# 4022_counter.net
KiCad netlist of a schematic drawn in EAGLE
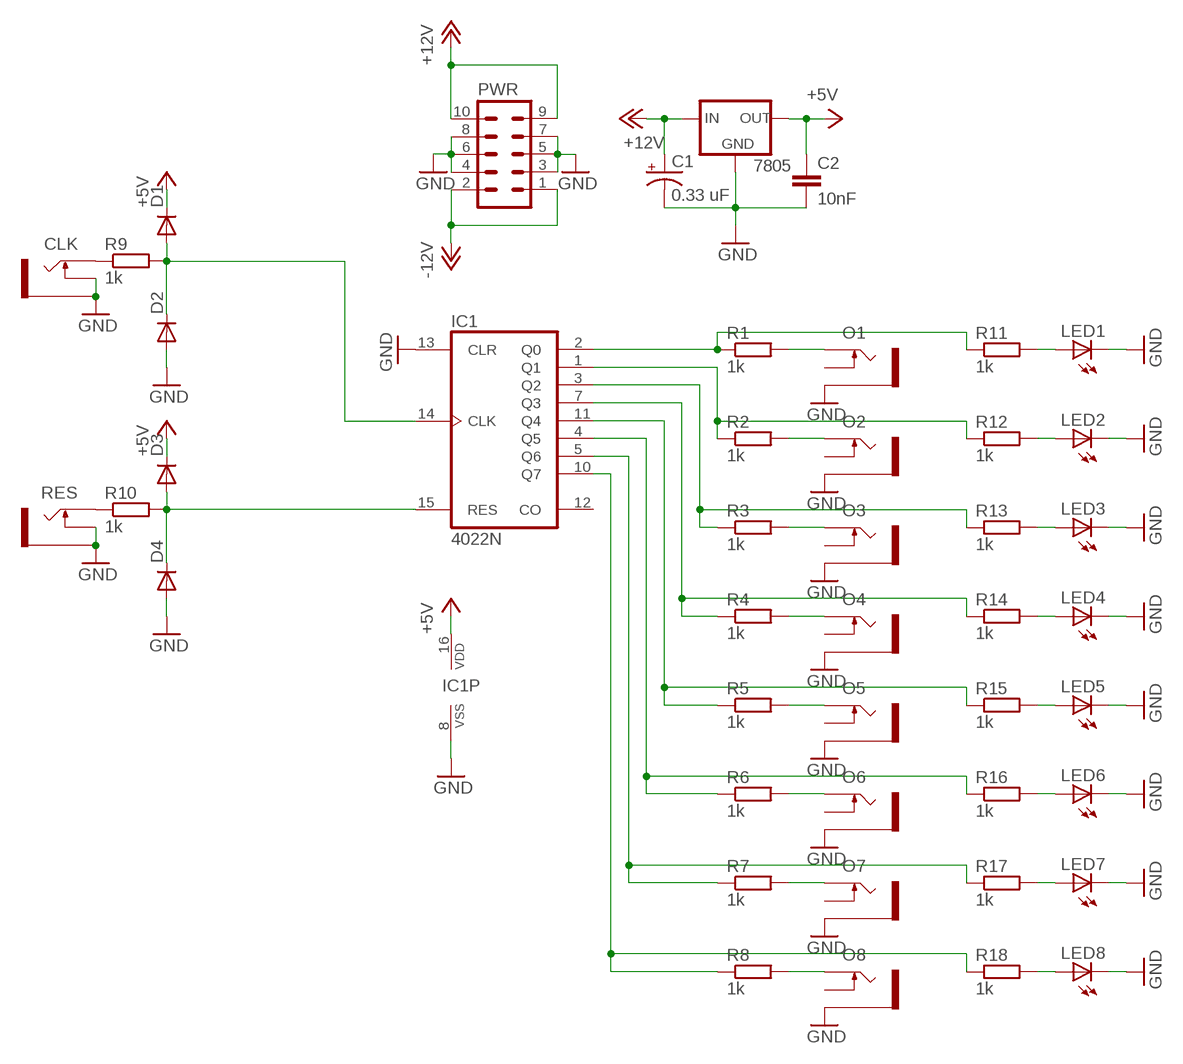
[diagram p0: schematic, sheet 1]

(export (version "E")
  (design (tool "Eeschema 10.0.6"))
  (components
    (comp (ref "7805")
      (value "78XXS")
      (footprint "eagle-import:78XXS")
      (libsource (lib "eagle-import") (part "78XXS"))
    )
    (comp (ref "C1")
      (value "0.33 uF")
      (footprint "eagle-import:E2,5-7")
      (libsource (lib "eagle-import") (part "CPOL-USE2.5-7"))
    )
    (comp (ref "C2")
      (value "10nF")
      (footprint "eagle-import:CAP-PTH-10MM")
      (libsource (lib "eagle-import") (part "10NF-PTH-10MM-10000V-1-%"))
    )
    (comp (ref "CLK")
      (value "THONKICONNNEW")
      (footprint "eagle-import:WQP-PJ301M-12_JACK")
      (libsource (lib "eagle-import") (part "THONKICONNNEW"))
    )
    (comp (ref "D1")
      (value "SMALL_DIODEDO35-7")
      (footprint "eagle-import:DO35-7")
      (libsource (lib "eagle-import") (part "SMALL_DIODEDO35-7"))
    )
    (comp (ref "D2")
      (value "SMALL_DIODEDO35-7")
      (footprint "eagle-import:DO35-7")
      (libsource (lib "eagle-import") (part "SMALL_DIODEDO35-7"))
    )
    (comp (ref "D3")
      (value "SMALL_DIODEDO35-7")
      (footprint "eagle-import:DO35-7")
      (libsource (lib "eagle-import") (part "SMALL_DIODEDO35-7"))
    )
    (comp (ref "D4")
      (value "SMALL_DIODEDO35-7")
      (footprint "eagle-import:DO35-7")
      (libsource (lib "eagle-import") (part "SMALL_DIODEDO35-7"))
    )
    (comp (ref "IC1")
      (value "4022N")
      (footprint "eagle-import:DIL16")
      (libsource (lib "eagle-import") (part "4022N"))
    )
    (comp (ref "LED1")
      (value "LED3MM")
      (footprint "eagle-import:LED3MM")
      (libsource (lib "eagle-import") (part "LED3MM"))
    )
    (comp (ref "LED2")
      (value "LED3MM")
      (footprint "eagle-import:LED3MM")
      (libsource (lib "eagle-import") (part "LED3MM"))
    )
    (comp (ref "LED3")
      (value "LED3MM")
      (footprint "eagle-import:LED3MM")
      (libsource (lib "eagle-import") (part "LED3MM"))
    )
    (comp (ref "LED4")
      (value "LED3MM")
      (footprint "eagle-import:LED3MM")
      (libsource (lib "eagle-import") (part "LED3MM"))
    )
    (comp (ref "LED5")
      (value "LED3MM")
      (footprint "eagle-import:LED3MM")
      (libsource (lib "eagle-import") (part "LED3MM"))
    )
    (comp (ref "LED6")
      (value "LED3MM")
      (footprint "eagle-import:LED3MM")
      (libsource (lib "eagle-import") (part "LED3MM"))
    )
    (comp (ref "LED7")
      (value "LED3MM")
      (footprint "eagle-import:LED3MM")
      (libsource (lib "eagle-import") (part "LED3MM"))
    )
    (comp (ref "LED8")
      (value "LED3MM")
      (footprint "eagle-import:LED3MM")
      (libsource (lib "eagle-import") (part "LED3MM"))
    )
    (comp (ref "O1")
      (value "THONKICONNNEW")
      (footprint "eagle-import:WQP-PJ301M-12_JACK")
      (libsource (lib "eagle-import") (part "THONKICONNNEW"))
    )
    (comp (ref "O2")
      (value "THONKICONNNEW")
      (footprint "eagle-import:WQP-PJ301M-12_JACK")
      (libsource (lib "eagle-import") (part "THONKICONNNEW"))
    )
    (comp (ref "O3")
      (value "THONKICONNNEW")
      (footprint "eagle-import:WQP-PJ301M-12_JACK")
      (libsource (lib "eagle-import") (part "THONKICONNNEW"))
    )
    (comp (ref "O4")
      (value "THONKICONNNEW")
      (footprint "eagle-import:WQP-PJ301M-12_JACK")
      (libsource (lib "eagle-import") (part "THONKICONNNEW"))
    )
    (comp (ref "O5")
      (value "THONKICONNNEW")
      (footprint "eagle-import:WQP-PJ301M-12_JACK")
      (libsource (lib "eagle-import") (part "THONKICONNNEW"))
    )
    (comp (ref "O6")
      (value "THONKICONNNEW")
      (footprint "eagle-import:WQP-PJ301M-12_JACK")
      (libsource (lib "eagle-import") (part "THONKICONNNEW"))
    )
    (comp (ref "O7")
      (value "THONKICONNNEW")
      (footprint "eagle-import:WQP-PJ301M-12_JACK")
      (libsource (lib "eagle-import") (part "THONKICONNNEW"))
    )
    (comp (ref "O8")
      (value "THONKICONNNEW")
      (footprint "eagle-import:WQP-PJ301M-12_JACK")
      (libsource (lib "eagle-import") (part "THONKICONNNEW"))
    )
    (comp (ref "PWR")
      (value "EURO_POWER_HEADERFAT_PADS")
      (footprint "eagle-import:EURO_PWR_HEADER_FAT")
      (libsource (lib "eagle-import") (part "EURO_POWER_HEADERFAT_PADS"))
    )
    (comp (ref "R1")
      (value "1k")
      (footprint "eagle-import:7MM_RESISTOR")
      (libsource (lib "eagle-import") (part "RESISTOR7MM"))
    )
    (comp (ref "R2")
      (value "1k")
      (footprint "eagle-import:7MM_RESISTOR")
      (libsource (lib "eagle-import") (part "RESISTOR7MM"))
    )
    (comp (ref "R3")
      (value "1k")
      (footprint "eagle-import:7MM_RESISTOR")
      (libsource (lib "eagle-import") (part "RESISTOR7MM"))
    )
    (comp (ref "R4")
      (value "1k")
      (footprint "eagle-import:7MM_RESISTOR")
      (libsource (lib "eagle-import") (part "RESISTOR7MM"))
    )
    (comp (ref "R5")
      (value "1k")
      (footprint "eagle-import:7MM_RESISTOR")
      (libsource (lib "eagle-import") (part "RESISTOR7MM"))
    )
    (comp (ref "R6")
      (value "1k")
      (footprint "eagle-import:7MM_RESISTOR")
      (libsource (lib "eagle-import") (part "RESISTOR7MM"))
    )
    (comp (ref "R7")
      (value "1k")
      (footprint "eagle-import:7MM_RESISTOR")
      (libsource (lib "eagle-import") (part "RESISTOR7MM"))
    )
    (comp (ref "R8")
      (value "1k")
      (footprint "eagle-import:7MM_RESISTOR")
      (libsource (lib "eagle-import") (part "RESISTOR7MM"))
    )
    (comp (ref "R9")
      (value "1k")
      (footprint "eagle-import:7MM_RESISTOR")
      (libsource (lib "eagle-import") (part "RESISTOR7MM"))
    )
    (comp (ref "R10")
      (value "1k")
      (footprint "eagle-import:7MM_RESISTOR")
      (libsource (lib "eagle-import") (part "RESISTOR7MM"))
    )
    (comp (ref "R11")
      (value "1k")
      (footprint "eagle-import:7MM_RESISTOR")
      (libsource (lib "eagle-import") (part "RESISTOR7MM"))
    )
    (comp (ref "R12")
      (value "1k")
      (footprint "eagle-import:7MM_RESISTOR")
      (libsource (lib "eagle-import") (part "RESISTOR7MM"))
    )
    (comp (ref "R13")
      (value "1k")
      (footprint "eagle-import:7MM_RESISTOR")
      (libsource (lib "eagle-import") (part "RESISTOR7MM"))
    )
    (comp (ref "R14")
      (value "1k")
      (footprint "eagle-import:7MM_RESISTOR")
      (libsource (lib "eagle-import") (part "RESISTOR7MM"))
    )
    (comp (ref "R15")
      (value "1k")
      (footprint "eagle-import:7MM_RESISTOR")
      (libsource (lib "eagle-import") (part "RESISTOR7MM"))
    )
    (comp (ref "R16")
      (value "1k")
      (footprint "eagle-import:7MM_RESISTOR")
      (libsource (lib "eagle-import") (part "RESISTOR7MM"))
    )
    (comp (ref "R17")
      (value "1k")
      (footprint "eagle-import:7MM_RESISTOR")
      (libsource (lib "eagle-import") (part "RESISTOR7MM"))
    )
    (comp (ref "R18")
      (value "1k")
      (footprint "eagle-import:7MM_RESISTOR")
      (libsource (lib "eagle-import") (part "RESISTOR7MM"))
    )
    (comp (ref "RES")
      (value "THONKICONNNEW")
      (footprint "eagle-import:WQP-PJ301M-12_JACK")
      (libsource (lib "eagle-import") (part "THONKICONNNEW"))
    )
  )
  (nets
    (net (code "1") (name "+5V") (class "Default")
      (node (ref "7805") (pin "OUT") (pinfunction "OUT_OUT") (pintype "passive"))
      (node (ref "C2") (pin "1") (pinfunction "1_1") (pintype "passive"))
      (node (ref "D1") (pin "C") (pinfunction "C_C") (pintype "passive"))
      (node (ref "D3") (pin "C") (pinfunction "C_C") (pintype "passive"))
      (node (ref "IC1") (pin "16") (pinfunction "VDD_16") (pintype "power_in"))
    )
    (net (code "2") (name "+12V") (class "Default")
      (node (ref "7805") (pin "IN") (pinfunction "IN_IN") (pintype "input"))
      (node (ref "C1") (pin "+") (pinfunction "+_+") (pintype "passive"))
      (node (ref "PWR") (pin "10") (pinfunction "10_10") (pintype "passive"))
      (node (ref "PWR") (pin "9") (pinfunction "9_9") (pintype "passive"))
    )
    (net (code "3") (name "-12V") (class "Default")
      (node (ref "PWR") (pin "1") (pinfunction "1_1") (pintype "passive"))
      (node (ref "PWR") (pin "2") (pinfunction "2_2") (pintype "passive"))
    )
    (net (code "4") (name "GND") (class "Default")
      (node (ref "7805") (pin "GND") (pinfunction "GND_GND") (pintype "input"))
      (node (ref "C1") (pin "-") (pinfunction "-_-") (pintype "passive"))
      (node (ref "C2") (pin "2") (pinfunction "2_2") (pintype "passive"))
      (node (ref "CLK") (pin "P$2_SWITCH") (pinfunction "SWITCH_P$2_SWITCH") (pintype "passive"))
      (node (ref "CLK") (pin "P$3_SLEEVE") (pinfunction "SLEEVE_P$3_SLEEVE") (pintype "passive"))
      (node (ref "D2") (pin "A") (pinfunction "A_A") (pintype "passive"))
      (node (ref "D4") (pin "A") (pinfunction "A_A") (pintype "passive"))
      (node (ref "IC1") (pin "13") (pinfunction "CLR_13") (pintype "input"))
      (node (ref "IC1") (pin "8") (pinfunction "VSS_8") (pintype "power_in"))
      (node (ref "LED1") (pin "K") (pinfunction "C_K") (pintype "passive"))
      (node (ref "LED2") (pin "K") (pinfunction "C_K") (pintype "passive"))
      (node (ref "LED3") (pin "K") (pinfunction "C_K") (pintype "passive"))
      (node (ref "LED4") (pin "K") (pinfunction "C_K") (pintype "passive"))
      (node (ref "LED5") (pin "K") (pinfunction "C_K") (pintype "passive"))
      (node (ref "LED6") (pin "K") (pinfunction "C_K") (pintype "passive"))
      (node (ref "LED7") (pin "K") (pinfunction "C_K") (pintype "passive"))
      (node (ref "LED8") (pin "K") (pinfunction "C_K") (pintype "passive"))
      (node (ref "O1") (pin "P$3_SLEEVE") (pinfunction "SLEEVE_P$3_SLEEVE") (pintype "passive"))
      (node (ref "O2") (pin "P$3_SLEEVE") (pinfunction "SLEEVE_P$3_SLEEVE") (pintype "passive"))
      (node (ref "O3") (pin "P$3_SLEEVE") (pinfunction "SLEEVE_P$3_SLEEVE") (pintype "passive"))
      (node (ref "O4") (pin "P$3_SLEEVE") (pinfunction "SLEEVE_P$3_SLEEVE") (pintype "passive"))
      (node (ref "O5") (pin "P$3_SLEEVE") (pinfunction "SLEEVE_P$3_SLEEVE") (pintype "passive"))
      (node (ref "O6") (pin "P$3_SLEEVE") (pinfunction "SLEEVE_P$3_SLEEVE") (pintype "passive"))
      (node (ref "O7") (pin "P$3_SLEEVE") (pinfunction "SLEEVE_P$3_SLEEVE") (pintype "passive"))
      (node (ref "O8") (pin "P$3_SLEEVE") (pinfunction "SLEEVE_P$3_SLEEVE") (pintype "passive"))
      (node (ref "PWR") (pin "3") (pinfunction "3_3") (pintype "passive"))
      (node (ref "PWR") (pin "4") (pinfunction "4_4") (pintype "passive"))
      (node (ref "PWR") (pin "5") (pinfunction "5_5") (pintype "passive"))
      (node (ref "PWR") (pin "6") (pinfunction "6_6") (pintype "passive"))
      (node (ref "PWR") (pin "7") (pinfunction "7_7") (pintype "passive"))
      (node (ref "PWR") (pin "8") (pinfunction "8_8") (pintype "passive"))
      (node (ref "RES") (pin "P$2_SWITCH") (pinfunction "SWITCH_P$2_SWITCH") (pintype "passive"))
      (node (ref "RES") (pin "P$3_SLEEVE") (pinfunction "SLEEVE_P$3_SLEEVE") (pintype "passive"))
    )
    (net (code "5") (name "Net-(CLK-TIP)") (class "Default")
      (node (ref "CLK") (pin "P$1_TIP") (pinfunction "TIP_P$1_TIP") (pintype "passive"))
      (node (ref "R9") (pin "1") (pinfunction "1_1") (pintype "passive"))
    )
    (net (code "6") (name "Net-(IC1A-CLK)") (class "Default")
      (node (ref "D1") (pin "A") (pinfunction "A_A") (pintype "passive"))
      (node (ref "D2") (pin "C") (pinfunction "C_C") (pintype "passive"))
      (node (ref "IC1") (pin "14") (pinfunction "CLK_14") (pintype "input"))
      (node (ref "R9") (pin "2") (pinfunction "2_2") (pintype "passive"))
    )
    (net (code "7") (name "Net-(IC1A-Q0)") (class "Default")
      (node (ref "IC1") (pin "2") (pinfunction "Q0_2") (pintype "output"))
      (node (ref "R1") (pin "1") (pinfunction "1_1") (pintype "passive"))
      (node (ref "R11") (pin "1") (pinfunction "1_1") (pintype "passive"))
    )
    (net (code "8") (name "Net-(IC1A-Q1)") (class "Default")
      (node (ref "IC1") (pin "1") (pinfunction "Q1_1") (pintype "output"))
      (node (ref "R12") (pin "1") (pinfunction "1_1") (pintype "passive"))
      (node (ref "R2") (pin "1") (pinfunction "1_1") (pintype "passive"))
    )
    (net (code "9") (name "Net-(IC1A-Q2)") (class "Default")
      (node (ref "IC1") (pin "3") (pinfunction "Q2_3") (pintype "output"))
      (node (ref "R13") (pin "1") (pinfunction "1_1") (pintype "passive"))
      (node (ref "R3") (pin "1") (pinfunction "1_1") (pintype "passive"))
    )
    (net (code "10") (name "Net-(IC1A-Q3)") (class "Default")
      (node (ref "IC1") (pin "7") (pinfunction "Q3_7") (pintype "output"))
      (node (ref "R14") (pin "1") (pinfunction "1_1") (pintype "passive"))
      (node (ref "R4") (pin "1") (pinfunction "1_1") (pintype "passive"))
    )
    (net (code "11") (name "Net-(IC1A-Q4)") (class "Default")
      (node (ref "IC1") (pin "11") (pinfunction "Q4_11") (pintype "output"))
      (node (ref "R15") (pin "1") (pinfunction "1_1") (pintype "passive"))
      (node (ref "R5") (pin "1") (pinfunction "1_1") (pintype "passive"))
    )
    (net (code "12") (name "Net-(IC1A-Q5)") (class "Default")
      (node (ref "IC1") (pin "4") (pinfunction "Q5_4") (pintype "output"))
      (node (ref "R16") (pin "1") (pinfunction "1_1") (pintype "passive"))
      (node (ref "R6") (pin "1") (pinfunction "1_1") (pintype "passive"))
    )
    (net (code "13") (name "Net-(IC1A-Q6)") (class "Default")
      (node (ref "IC1") (pin "5") (pinfunction "Q6_5") (pintype "output"))
      (node (ref "R17") (pin "1") (pinfunction "1_1") (pintype "passive"))
      (node (ref "R7") (pin "1") (pinfunction "1_1") (pintype "passive"))
    )
    (net (code "14") (name "Net-(IC1A-Q7)") (class "Default")
      (node (ref "IC1") (pin "10") (pinfunction "Q7_10") (pintype "output"))
      (node (ref "R18") (pin "1") (pinfunction "1_1") (pintype "passive"))
      (node (ref "R8") (pin "1") (pinfunction "1_1") (pintype "passive"))
    )
    (net (code "15") (name "Net-(IC1A-RES)") (class "Default")
      (node (ref "D3") (pin "A") (pinfunction "A_A") (pintype "passive"))
      (node (ref "D4") (pin "C") (pinfunction "C_C") (pintype "passive"))
      (node (ref "IC1") (pin "15") (pinfunction "RES_15") (pintype "input"))
      (node (ref "R10") (pin "2") (pinfunction "2_2") (pintype "passive"))
    )
    (net (code "16") (name "Net-(LED1-PadA)") (class "Default")
      (node (ref "LED1") (pin "A") (pinfunction "A_A") (pintype "passive"))
      (node (ref "R11") (pin "2") (pinfunction "2_2") (pintype "passive"))
    )
    (net (code "17") (name "Net-(LED2-PadA)") (class "Default")
      (node (ref "LED2") (pin "A") (pinfunction "A_A") (pintype "passive"))
      (node (ref "R12") (pin "2") (pinfunction "2_2") (pintype "passive"))
    )
    (net (code "18") (name "Net-(LED3-PadA)") (class "Default")
      (node (ref "LED3") (pin "A") (pinfunction "A_A") (pintype "passive"))
      (node (ref "R13") (pin "2") (pinfunction "2_2") (pintype "passive"))
    )
    (net (code "19") (name "Net-(LED4-PadA)") (class "Default")
      (node (ref "LED4") (pin "A") (pinfunction "A_A") (pintype "passive"))
      (node (ref "R14") (pin "2") (pinfunction "2_2") (pintype "passive"))
    )
    (net (code "20") (name "Net-(LED5-PadA)") (class "Default")
      (node (ref "LED5") (pin "A") (pinfunction "A_A") (pintype "passive"))
      (node (ref "R15") (pin "2") (pinfunction "2_2") (pintype "passive"))
    )
    (net (code "21") (name "Net-(LED6-PadA)") (class "Default")
      (node (ref "LED6") (pin "A") (pinfunction "A_A") (pintype "passive"))
      (node (ref "R16") (pin "2") (pinfunction "2_2") (pintype "passive"))
    )
    (net (code "22") (name "Net-(LED7-PadA)") (class "Default")
      (node (ref "LED7") (pin "A") (pinfunction "A_A") (pintype "passive"))
      (node (ref "R17") (pin "2") (pinfunction "2_2") (pintype "passive"))
    )
    (net (code "23") (name "Net-(LED8-PadA)") (class "Default")
      (node (ref "LED8") (pin "A") (pinfunction "A_A") (pintype "passive"))
      (node (ref "R18") (pin "2") (pinfunction "2_2") (pintype "passive"))
    )
    (net (code "24") (name "Net-(O1-TIP)") (class "Default")
      (node (ref "O1") (pin "P$1_TIP") (pinfunction "TIP_P$1_TIP") (pintype "passive"))
      (node (ref "R1") (pin "2") (pinfunction "2_2") (pintype "passive"))
    )
    (net (code "25") (name "Net-(O2-TIP)") (class "Default")
      (node (ref "O2") (pin "P$1_TIP") (pinfunction "TIP_P$1_TIP") (pintype "passive"))
      (node (ref "R2") (pin "2") (pinfunction "2_2") (pintype "passive"))
    )
    (net (code "26") (name "Net-(O3-TIP)") (class "Default")
      (node (ref "O3") (pin "P$1_TIP") (pinfunction "TIP_P$1_TIP") (pintype "passive"))
      (node (ref "R3") (pin "2") (pinfunction "2_2") (pintype "passive"))
    )
    (net (code "27") (name "Net-(O4-TIP)") (class "Default")
      (node (ref "O4") (pin "P$1_TIP") (pinfunction "TIP_P$1_TIP") (pintype "passive"))
      (node (ref "R4") (pin "2") (pinfunction "2_2") (pintype "passive"))
    )
    (net (code "28") (name "Net-(O5-TIP)") (class "Default")
      (node (ref "O5") (pin "P$1_TIP") (pinfunction "TIP_P$1_TIP") (pintype "passive"))
      (node (ref "R5") (pin "2") (pinfunction "2_2") (pintype "passive"))
    )
    (net (code "29") (name "Net-(O6-TIP)") (class "Default")
      (node (ref "O6") (pin "P$1_TIP") (pinfunction "TIP_P$1_TIP") (pintype "passive"))
      (node (ref "R6") (pin "2") (pinfunction "2_2") (pintype "passive"))
    )
    (net (code "30") (name "Net-(O7-TIP)") (class "Default")
      (node (ref "O7") (pin "P$1_TIP") (pinfunction "TIP_P$1_TIP") (pintype "passive"))
      (node (ref "R7") (pin "2") (pinfunction "2_2") (pintype "passive"))
    )
    (net (code "31") (name "Net-(O8-TIP)") (class "Default")
      (node (ref "O8") (pin "P$1_TIP") (pinfunction "TIP_P$1_TIP") (pintype "passive"))
      (node (ref "R8") (pin "2") (pinfunction "2_2") (pintype "passive"))
    )
    (net (code "32") (name "Net-(RES-TIP)") (class "Default")
      (node (ref "R10") (pin "1") (pinfunction "1_1") (pintype "passive"))
      (node (ref "RES") (pin "P$1_TIP") (pinfunction "TIP_P$1_TIP") (pintype "passive"))
    )
    (net (code "33") (name "unconnected-(IC1A-CO-Pad12)") (class "Default")
      (node (ref "IC1") (pin "12") (pinfunction "CO_12") (pintype "output"))
    )
    (net (code "34") (name "unconnected-(O1-SWITCH-PadP$2_SWITCH)") (class "Default")
      (node (ref "O1") (pin "P$2_SWITCH") (pinfunction "SWITCH_P$2_SWITCH") (pintype "passive"))
    )
    (net (code "35") (name "unconnected-(O2-SWITCH-PadP$2_SWITCH)") (class "Default")
      (node (ref "O2") (pin "P$2_SWITCH") (pinfunction "SWITCH_P$2_SWITCH") (pintype "passive"))
    )
    (net (code "36") (name "unconnected-(O3-SWITCH-PadP$2_SWITCH)") (class "Default")
      (node (ref "O3") (pin "P$2_SWITCH") (pinfunction "SWITCH_P$2_SWITCH") (pintype "passive"))
    )
    (net (code "37") (name "unconnected-(O4-SWITCH-PadP$2_SWITCH)") (class "Default")
      (node (ref "O4") (pin "P$2_SWITCH") (pinfunction "SWITCH_P$2_SWITCH") (pintype "passive"))
    )
    (net (code "38") (name "unconnected-(O5-SWITCH-PadP$2_SWITCH)") (class "Default")
      (node (ref "O5") (pin "P$2_SWITCH") (pinfunction "SWITCH_P$2_SWITCH") (pintype "passive"))
    )
    (net (code "39") (name "unconnected-(O6-SWITCH-PadP$2_SWITCH)") (class "Default")
      (node (ref "O6") (pin "P$2_SWITCH") (pinfunction "SWITCH_P$2_SWITCH") (pintype "passive"))
    )
    (net (code "40") (name "unconnected-(O7-SWITCH-PadP$2_SWITCH)") (class "Default")
      (node (ref "O7") (pin "P$2_SWITCH") (pinfunction "SWITCH_P$2_SWITCH") (pintype "passive"))
    )
    (net (code "41") (name "unconnected-(O8-SWITCH-PadP$2_SWITCH)") (class "Default")
      (node (ref "O8") (pin "P$2_SWITCH") (pinfunction "SWITCH_P$2_SWITCH") (pintype "passive"))
    )
  )
)
